# esp-relay.net
KiCad netlist of a schematic drawn in Altium Designer
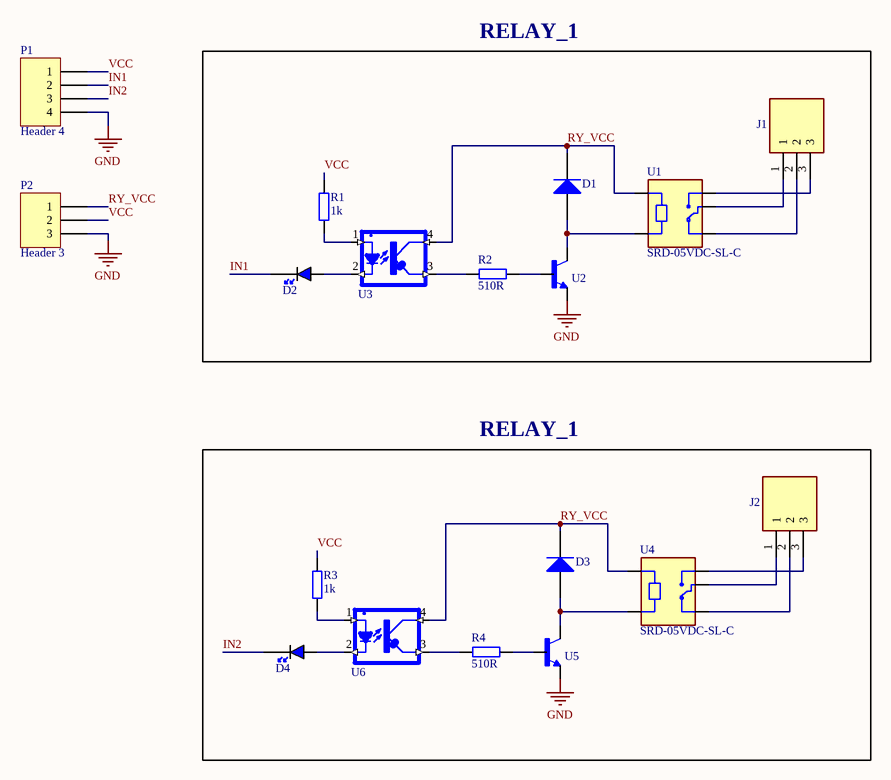
[diagram p0: esp-relay.SchDoc]

(export (version "E")
  (design (tool "Eeschema 10.0.6"))
  (components
    (comp (ref "D1")
      (value "Diode 1N4003")
      (footprint "DO-41")
      (description "1 Amp General Purpose Rectifier")
      (fields (field (name "PUBLISHER") "Altium Limited"))
      (libsource (lib "Miscellaneous Devices") (part "Diode 1N4003"))
    )
    (comp (ref "D2")
      (value "BLUE")
      (footprint "LED_0603_BLUE")
      (description "LED 0603 BLUE SMD")
      (libsource (lib "Schematic-Lib-sinan_savci") (part "LED_0603_BLUE"))
    )
    (comp (ref "D3")
      (value "Diode 1N4003")
      (footprint "DO-41")
      (description "1 Amp General Purpose Rectifier")
      (fields (field (name "PUBLISHER") "Altium Limited"))
      (libsource (lib "Miscellaneous Devices") (part "Diode 1N4003"))
    )
    (comp (ref "D4")
      (value "BLUE")
      (footprint "LED_0603_BLUE")
      (description "LED 0603 BLUE SMD")
      (libsource (lib "Schematic-Lib-sinan_savci") (part "LED_0603_BLUE"))
    )
    (comp (ref "J1")
      (value "Terminal Block Connector")
      (footprint "TB006-508-03BE")
      (description "2~24 Poles, Screw Type, Horizontal, 5.08 Pitch, 26~14 (AWG), Terminal Block Connector")
      (libsource (lib "Schematic-Lib-sinan_savci") (part "TB006-508-03BE"))
    )
    (comp (ref "J2")
      (value "Terminal Block Connector")
      (footprint "TB006-508-03BE")
      (description "2~24 Poles, Screw Type, Horizontal, 5.08 Pitch, 26~14 (AWG), Terminal Block Connector")
      (libsource (lib "Schematic-Lib-sinan_savci") (part "TB006-508-03BE"))
    )
    (comp (ref "P1")
      (value "Header 4")
      (footprint "HDR1X4")
      (description "Header, 4-Pin")
      (fields (field (name "PUBLISHER") "Altium Limited"))
      (libsource (lib "Miscellaneous Connectors") (part "Header 4"))
    )
    (comp (ref "P2")
      (value "Header 3")
      (footprint "HDR1X3")
      (description "Header, 3-Pin")
      (fields (field (name "PUBLISHER") "Altium Limited"))
      (libsource (lib "Miscellaneous Connectors") (part "Header 3"))
    )
    (comp (ref "R1")
      (value "1k")
      (footprint "RES_1206")
      (description "Resistor SMD 1206")
      (libsource (lib "Schematic-Lib-sinan_savci") (part "RES_1206"))
    )
    (comp (ref "R2")
      (value "510R")
      (footprint "RES_1206")
      (description "Resistor SMD 1206")
      (libsource (lib "Schematic-Lib-sinan_savci") (part "RES_1206"))
    )
    (comp (ref "R3")
      (value "1k")
      (footprint "RES_1206")
      (description "Resistor SMD 1206")
      (libsource (lib "Schematic-Lib-sinan_savci") (part "RES_1206"))
    )
    (comp (ref "R4")
      (value "510R")
      (footprint "RES_1206")
      (description "Resistor SMD 1206")
      (libsource (lib "Schematic-Lib-sinan_savci") (part "RES_1206"))
    )
    (comp (ref "U1")
      (value "SRD-05VDC-SL-C")
      (footprint "RELAY_SRD-03VDC-SL-C")
      (libsource (lib "Schematic-Lib-sinan_savci") (part "Relay-Songle"))
    )
    (comp (ref "U2")
      (value "BCW31 NPN")
      (footprint "SOT23")
      (description "Bipolar (BJT) Transistor NPN General Purpose Amplifier Surface Mount")
      (libsource (lib "Schematic-Lib-sinan_savci") (part "BCW31 NPN"))
    )
    (comp (ref "U3")
      (value "LTV-817")
      (footprint "DIP-4")
      (description "Optocouplor")
      (libsource (lib "Schematic-Lib-sinan_savci") (part "LTV-817"))
    )
    (comp (ref "U4")
      (value "SRD-05VDC-SL-C")
      (footprint "RELAY_SRD-03VDC-SL-C")
      (libsource (lib "Schematic-Lib-sinan_savci") (part "Relay-Songle"))
    )
    (comp (ref "U5")
      (value "BCW31 NPN")
      (footprint "SOT23")
      (description "Bipolar (BJT) Transistor NPN General Purpose Amplifier Surface Mount")
      (libsource (lib "Schematic-Lib-sinan_savci") (part "BCW31 NPN"))
    )
    (comp (ref "U6")
      (value "LTV-817")
      (footprint "DIP-4")
      (description "Optocouplor")
      (libsource (lib "Schematic-Lib-sinan_savci") (part "LTV-817"))
    )
  )
  (nets
    (net (code "1") (name "/IN1") (class "Default")
      (node (ref "D2") (pin "K") (pinfunction "K_K") (pintype "passive"))
      (node (ref "P1") (pin "2") (pinfunction "2_2") (pintype "passive"))
    )
    (net (code "2") (name "/IN2") (class "Default")
      (node (ref "D4") (pin "K") (pinfunction "K_K") (pintype "passive"))
      (node (ref "P1") (pin "3") (pinfunction "3_3") (pintype "passive"))
    )
    (net (code "3") (name "/RY_VCC") (class "Default")
      (node (ref "D1") (pin "2") (pinfunction "K_2") (pintype "passive"))
      (node (ref "D3") (pin "2") (pinfunction "K_2") (pintype "passive"))
      (node (ref "P2") (pin "1") (pinfunction "1_1") (pintype "passive"))
      (node (ref "U1") (pin "A1") (pinfunction "A1_A1") (pintype "passive"))
      (node (ref "U3") (pin "4") (pinfunction "4_4") (pintype "input"))
      (node (ref "U4") (pin "A1") (pinfunction "A1_A1") (pintype "passive"))
      (node (ref "U6") (pin "4") (pinfunction "4_4") (pintype "input"))
    )
    (net (code "4") (name "/VCC") (class "Default")
      (node (ref "P1") (pin "1") (pinfunction "1_1") (pintype "passive"))
      (node (ref "P2") (pin "2") (pinfunction "2_2") (pintype "passive"))
      (node (ref "R1") (pin "2") (pinfunction "2_2") (pintype "passive"))
      (node (ref "R3") (pin "2") (pinfunction "2_2") (pintype "passive"))
    )
    (net (code "5") (name "GND") (class "Default")
      (node (ref "P1") (pin "4") (pinfunction "4_4") (pintype "passive"))
      (node (ref "P2") (pin "3") (pinfunction "3_3") (pintype "passive"))
      (node (ref "U2") (pin "E") (pinfunction "E_E") (pintype "passive"))
      (node (ref "U5") (pin "E") (pinfunction "E_E") (pintype "passive"))
    )
    (net (code "6") (name "Net-(D1-A)") (class "Default")
      (node (ref "D1") (pin "1") (pinfunction "A_1") (pintype "passive"))
      (node (ref "U1") (pin "A2") (pinfunction "A2_A2") (pintype "passive"))
      (node (ref "U2") (pin "C") (pinfunction "C_C") (pintype "passive"))
    )
    (net (code "7") (name "Net-(D2-PadA)") (class "Default")
      (node (ref "D2") (pin "A") (pinfunction "A_A") (pintype "passive"))
      (node (ref "U3") (pin "2") (pinfunction "2_2") (pintype "output"))
    )
    (net (code "8") (name "Net-(D3-A)") (class "Default")
      (node (ref "D3") (pin "1") (pinfunction "A_1") (pintype "passive"))
      (node (ref "U4") (pin "A2") (pinfunction "A2_A2") (pintype "passive"))
      (node (ref "U5") (pin "C") (pinfunction "C_C") (pintype "passive"))
    )
    (net (code "9") (name "Net-(D4-PadA)") (class "Default")
      (node (ref "D4") (pin "A") (pinfunction "A_A") (pintype "passive"))
      (node (ref "U6") (pin "2") (pinfunction "2_2") (pintype "output"))
    )
    (net (code "10") (name "Net-(J1-Pad1)") (class "Default")
      (node (ref "J1") (pin "1") (pinfunction "1_1") (pintype "passive"))
      (node (ref "U1") (pin "COM") (pinfunction "COM_COM") (pintype "passive"))
    )
    (net (code "11") (name "Net-(J1-Pad2)") (class "Default")
      (node (ref "J1") (pin "2") (pinfunction "2_2") (pintype "passive"))
      (node (ref "U1") (pin "NC") (pinfunction "NC_NC") (pintype "passive"))
    )
    (net (code "12") (name "Net-(J1-Pad3)") (class "Default")
      (node (ref "J1") (pin "3") (pinfunction "3_3") (pintype "passive"))
      (node (ref "U1") (pin "NO") (pinfunction "NO_NO") (pintype "passive"))
    )
    (net (code "13") (name "Net-(J2-Pad1)") (class "Default")
      (node (ref "J2") (pin "1") (pinfunction "1_1") (pintype "passive"))
      (node (ref "U4") (pin "COM") (pinfunction "COM_COM") (pintype "passive"))
    )
    (net (code "14") (name "Net-(J2-Pad2)") (class "Default")
      (node (ref "J2") (pin "2") (pinfunction "2_2") (pintype "passive"))
      (node (ref "U4") (pin "NC") (pinfunction "NC_NC") (pintype "passive"))
    )
    (net (code "15") (name "Net-(J2-Pad3)") (class "Default")
      (node (ref "J2") (pin "3") (pinfunction "3_3") (pintype "passive"))
      (node (ref "U4") (pin "NO") (pinfunction "NO_NO") (pintype "passive"))
    )
    (net (code "16") (name "Net-(R1-Pad1)") (class "Default")
      (node (ref "R1") (pin "1") (pinfunction "1_1") (pintype "passive"))
      (node (ref "U3") (pin "1") (pinfunction "1_1") (pintype "input"))
    )
    (net (code "17") (name "Net-(R2-Pad1)") (class "Default")
      (node (ref "R2") (pin "1") (pinfunction "1_1") (pintype "passive"))
      (node (ref "U2") (pin "B") (pinfunction "B_B") (pintype "passive"))
    )
    (net (code "18") (name "Net-(R2-Pad2)") (class "Default")
      (node (ref "R2") (pin "2") (pinfunction "2_2") (pintype "passive"))
      (node (ref "U3") (pin "3") (pinfunction "3_3") (pintype "output"))
    )
    (net (code "19") (name "Net-(R3-Pad1)") (class "Default")
      (node (ref "R3") (pin "1") (pinfunction "1_1") (pintype "passive"))
      (node (ref "U6") (pin "1") (pinfunction "1_1") (pintype "input"))
    )
    (net (code "20") (name "Net-(R4-Pad1)") (class "Default")
      (node (ref "R4") (pin "1") (pinfunction "1_1") (pintype "passive"))
      (node (ref "U5") (pin "B") (pinfunction "B_B") (pintype "passive"))
    )
    (net (code "21") (name "Net-(R4-Pad2)") (class "Default")
      (node (ref "R4") (pin "2") (pinfunction "2_2") (pintype "passive"))
      (node (ref "U6") (pin "3") (pinfunction "3_3") (pintype "output"))
    )
  )
)
